# Power_Management.net
KiCad netlist of a schematic drawn in Altium Designer
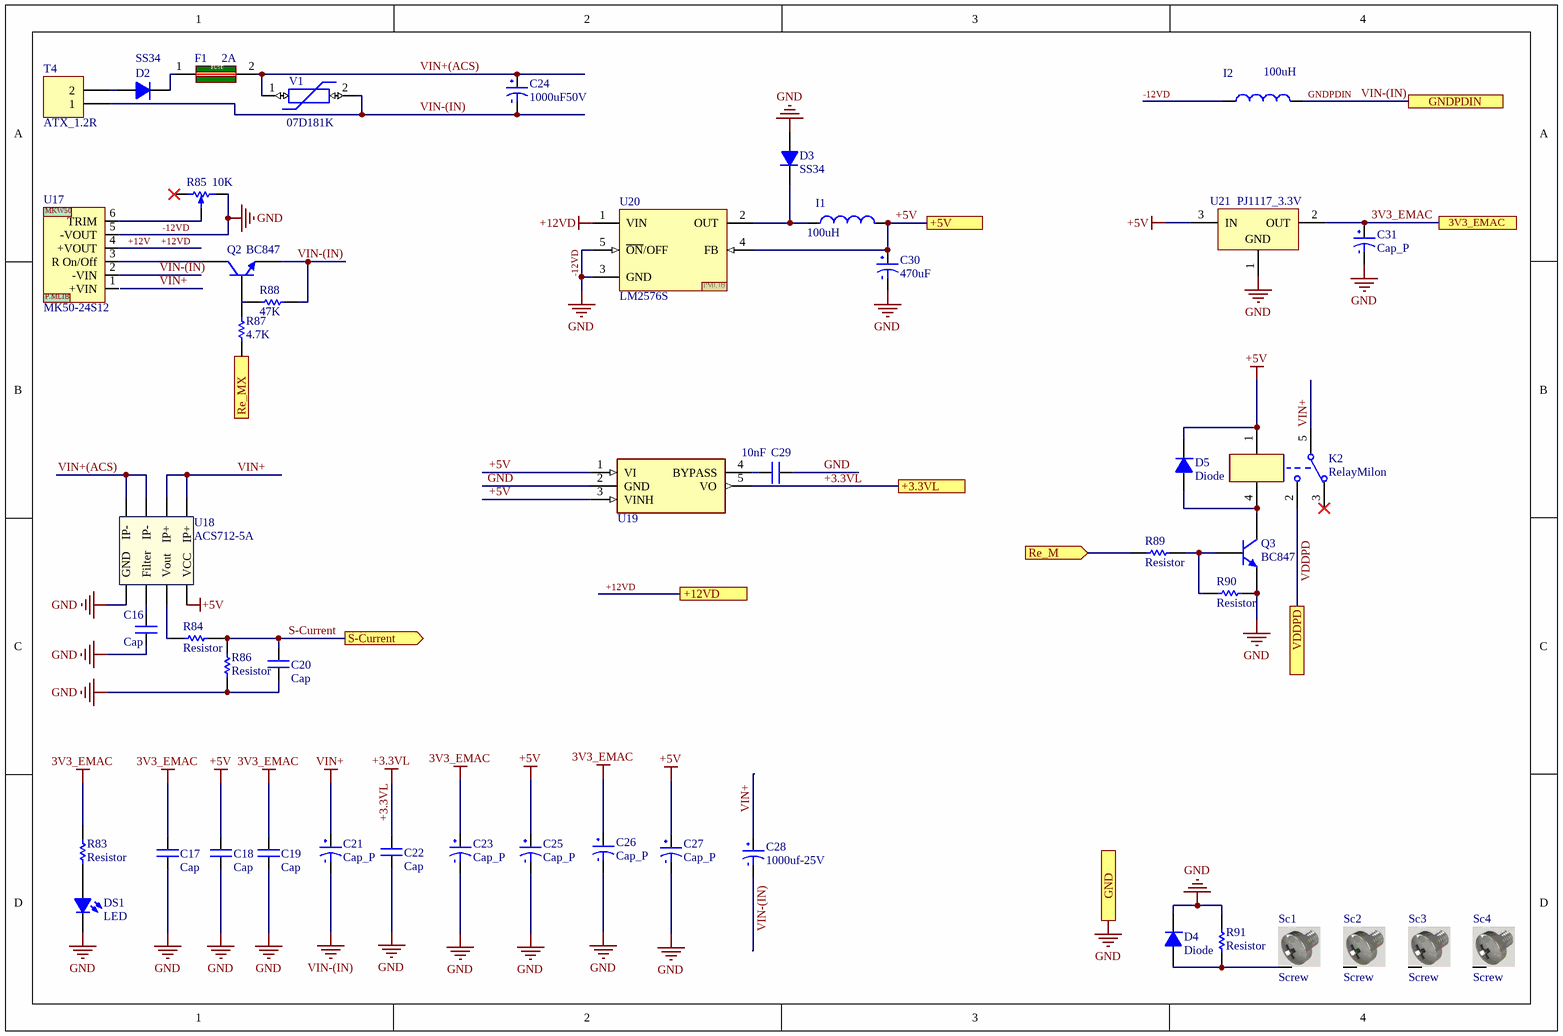
[diagram p0: Power Management.SchDoc]

(export (version "E")
  (design (tool "Eeschema 10.0.6"))
  (components
    (comp (ref "C16")
      (value "Cap")
      (footprint "Cap0805")
      (description "Surface mount Capacitor")
      (libsource (lib "PMLIB2020") (part "Cap"))
    )
    (comp (ref "C17")
      (value "Cap")
      (footprint "Cap0805")
      (description "Surface mount Capacitor")
      (libsource (lib "PMLIB2020") (part "Cap"))
    )
    (comp (ref "C18")
      (value "Cap")
      (footprint "Cap0805")
      (description "Surface mount Capacitor")
      (libsource (lib "PMLIB2020") (part "Cap"))
    )
    (comp (ref "C19")
      (value "Cap")
      (footprint "Cap0805")
      (description "Surface mount Capacitor")
      (libsource (lib "PMLIB2020") (part "Cap"))
    )
    (comp (ref "C20")
      (value "Cap")
      (footprint "Cap0805")
      (description "Surface mount Capacitor")
      (libsource (lib "PMLIB2020") (part "Cap"))
    )
    (comp (ref "C21")
      (value "Cap_P")
      (footprint "Cap_5mm")
      (description "Polarity")
      (libsource (lib "PMLIB2020") (part "Cap_P"))
    )
    (comp (ref "C22")
      (value "Cap")
      (footprint "Cap0805")
      (description "Surface mount Capacitor")
      (libsource (lib "PMLIB2020") (part "Cap"))
    )
    (comp (ref "C23")
      (value "Cap_P")
      (footprint "CAPMOL_C")
      (description "Polarity")
      (libsource (lib "PMLIB2020-V3") (part "Cap_P"))
    )
    (comp (ref "C24")
      (value "1000uF50V")
      (footprint "Cap_8mm")
      (description "Polarity")
      (libsource (lib "PMLIB2020-V3") (part "Cap_P"))
    )
    (comp (ref "C25")
      (value "Cap_P")
      (footprint "CAPMOL_C")
      (description "Polarity")
      (libsource (lib "PMLIB2020-V3") (part "Cap_P"))
    )
    (comp (ref "C26")
      (value "Cap_P")
      (footprint "CAPMOL_C")
      (description "Polarity")
      (libsource (lib "PMLIB2020-V3") (part "Cap_P"))
    )
    (comp (ref "C27")
      (value "Cap_P")
      (footprint "Cap_SMD")
      (description "Polarity")
      (libsource (lib "PMLIB2020-V3") (part "Cap_P"))
    )
    (comp (ref "C28")
      (value "1000uf-25V")
      (footprint "Cap_5mm")
      (description "Polarity")
      (libsource (lib "PMLIB2020") (part "Cap_P"))
    )
    (comp (ref "C29")
      (value "10nF")
      (footprint "Cap0805")
      (description "Surface mount Capacitor")
      (libsource (lib "PMLIB2020-V3") (part "Cap"))
    )
    (comp (ref "C30")
      (value "470uF")
      (footprint "Cap_4mm")
      (description "Polarity")
      (libsource (lib "PMLIB2020") (part "Cap_P"))
    )
    (comp (ref "C31")
      (value "Cap_P")
      (footprint "Cap_4mm")
      (description "Polarity")
      (libsource (lib "PMLIB2020") (part "Cap_P"))
    )
    (comp (ref "D2")
      (value "SS34")
      (footprint "Diod-1A-SMD")
      (description "Diode")
      (libsource (lib "PMLIB2020") (part "Diode"))
    )
    (comp (ref "D3")
      (value "SS34")
      (footprint "Diod-1A-SMD")
      (description "Diode")
      (libsource (lib "PMLIB2020") (part "Diode"))
    )
    (comp (ref "D4") (value "Diode") (footprint "Diod-1A-SMD") (libsource (lib "PMLIB2020") (part "Diode")))
    (comp (ref "D5")
      (value "Diode")
      (footprint "Diod-1A-SMD")
      (libsource (lib "PMLIB2020-V3") (part "Diode"))
    )
    (comp (ref "DS1") (value "LED") (footprint "Led0805") (libsource (lib "PMLIB2020") (part "LED")))
    (comp (ref "F1")
      (value "2A")
      (footprint "1206")
      (description "Fuse")
      (libsource (lib "PMLIB2020") (part "Fuse"))
    )
    (comp (ref "I1")
      (value "100uH")
      (footprint "Indicator_SMD")
      (description "Indicator")
      (libsource (lib "PMLIB2020") (part "Inductor"))
    )
    (comp (ref "I2")
      (value "100uH")
      (footprint "Indicator_10mH")
      (description "Indicator")
      (libsource (lib "PMLIB2020-V3") (part "Inductor"))
    )
    (comp (ref "K2")
      (value "RelayMilon")
      (footprint "RelayMinionSmall")
      (libsource (lib "PMLIB2020-V3") (part "RelayMilon"))
    )
    (comp (ref "Q2")
      (value "BC847")
      (footprint "SOT23_BEC_L")
      (description "NPN Bipolar Transistor")
      (fields (field (name "PUBLISHER") "Altium Limited"))
      (libsource (lib "PMLIB2020-V3") (part "NPN"))
    )
    (comp (ref "Q3")
      (value "BC847")
      (footprint "SOT23_BEC_L")
      (description "NPN Bipolar Transistor")
      (fields (field (name "PUBLISHER") "Altium Limited"))
      (libsource (lib "PMLIB2020-V3") (part "NPN"))
    )
    (comp (ref "R83") (value "Resistor") (footprint "R0805") (libsource (lib "PMLIB2020") (part "Resistor")))
    (comp (ref "R84") (value "Resistor") (footprint "R0805") (libsource (lib "PMLIB2020") (part "Resistor")))
    (comp (ref "R85")
      (value "10K")
      (footprint "POT4MM-Small Pot")
      (description "Square Trimming Potentiometer")
      (fields (field (name "Comment") "RPot SM") (field (name "PUBLISHER") "Altium Limited"))
      (libsource (lib "PMLIB2020-V3") (part "RPot SM"))
    )
    (comp (ref "R86") (value "Resistor") (footprint "R0805") (libsource (lib "PMLIB2020") (part "Resistor")))
    (comp (ref "R87")
      (value "4.7K")
      (footprint "R0805")
      (description "Resistor")
      (libsource (lib "PMLIB2020-V3") (part "Resistor"))
    )
    (comp (ref "R88")
      (value "47K")
      (footprint "R0805")
      (description "Resistor")
      (libsource (lib "PMLIB2020-V3") (part "Resistor"))
    )
    (comp (ref "R89")
      (value "Resistor")
      (footprint "R0805")
      (libsource (lib "PMLIB2020-V3") (part "Resistor"))
    )
    (comp (ref "R90")
      (value "Resistor")
      (footprint "R0805")
      (libsource (lib "PMLIB2020-V3") (part "Resistor"))
    )
    (comp (ref "R91") (value "Resistor") (footprint "0603") (libsource (lib "PMLIB2020") (part "Resistor")))
    (comp (ref "Sc1")
      (value "Screw")
      (footprint "Screw")
      (description "Screw 3mm")
      (libsource (lib "PMLIB2020") (part "Screw"))
    )
    (comp (ref "Sc2")
      (value "Screw")
      (footprint "Screw")
      (description "Screw 3mm")
      (libsource (lib "PMLIB2020") (part "Screw"))
    )
    (comp (ref "Sc3")
      (value "Screw")
      (footprint "Screw")
      (description "Screw 3mm")
      (libsource (lib "PMLIB2020") (part "Screw"))
    )
    (comp (ref "Sc4")
      (value "Screw")
      (footprint "Screw")
      (description "Screw 3mm")
      (libsource (lib "PMLIB2020") (part "Screw"))
    )
    (comp (ref "T4")
      (value "ATX_1.2R")
      (footprint "ATX_1.2S")
      (description "Connector")
      (libsource (lib "PMLIB2020-V3") (part "ATX_1.2R"))
    )
    (comp (ref "U17")
      (value "MK50-24S12")
      (footprint "MK50")
      (description "DCtoDC")
      (libsource (lib "PMLIB2020-V3") (part "MK50"))
    )
    (comp (ref "U18")
      (value "ACS712-5A")
      (footprint "SOP8")
      (description "Hall effect Current Sensor")
      (libsource (lib "PMLIB2020") (part "ACS712"))
    )
    (comp (ref "U19")
      (value "LD3985M33R")
      (footprint "SOT95P280X110-5N")
      (description "Linear Voltage Regulator IC 1 Output 150mA")
      (libsource (lib "PMLIB2020-V3") (part "LD3985M33R"))
    )
    (comp (ref "U20")
      (value "LM2576S")
      (footprint "LM2576S")
      (description "Regulator")
      (libsource (lib "PMLIB2020") (part "LM2576S"))
    )
    (comp (ref "U21")
      (value "PJ1117_3.3V")
      (footprint "PJ1117s")
      (description "Regulator")
      (libsource (lib "PMLIB2020-V3") (part "PJ1117_3.3V"))
    )
    (comp (ref "V1")
      (value "07D181K")
      (footprint "MOV-7D")
      (description "07D181K = 26V")
      (libsource (lib "PMLIB2020-V3") (part "MOV-07D"))
    )
  )
  (nets
    (net (code "1") (name "+3.3VL") (class "Default")
      (node (ref "C22") (pin "2") (pinfunction "2_2") (pintype "passive"))
      (node (ref "U19") (pin "5") (pinfunction "VO_5") (pintype "output"))
    )
    (net (code "2") (name "+5V") (class "Default")
      (node (ref "C18") (pin "2") (pinfunction "2_2") (pintype "passive"))
      (node (ref "C25") (pin "2") (pinfunction "2_2") (pintype "passive"))
      (node (ref "C27") (pin "2") (pinfunction "2_2") (pintype "passive"))
      (node (ref "C30") (pin "2") (pinfunction "2_2") (pintype "passive"))
      (node (ref "D5") (pin "K") (pinfunction "K_K") (pintype "passive"))
      (node (ref "I1") (pin "2") (pinfunction "2_2") (pintype "passive"))
      (node (ref "K2") (pin "1") (pinfunction "1_1") (pintype "passive"))
      (node (ref "U18") (pin "8") (pinfunction "VCC_8") (pintype "passive"))
      (node (ref "U19") (pin "1") (pinfunction "VI_1") (pintype "input"))
      (node (ref "U19") (pin "3") (pinfunction "VINH_3") (pintype "input"))
      (node (ref "U20") (pin "4") (pinfunction "FB_4") (pintype "input"))
      (node (ref "U21") (pin "3") (pinfunction "IN_3") (pintype "power_in"))
    )
    (net (code "3") (name "+12VD") (class "Default")
      (node (ref "U17") (pin "4") (pinfunction "+VOUT_4") (pintype "passive"))
      (node (ref "U20") (pin "1") (pinfunction "VIN_1") (pintype "power_in"))
    )
    (net (code "4") (name "/Re_M") (class "Default")
      (node (ref "R89") (pin "2") (pinfunction "2_2") (pintype "passive"))
    )
    (net (code "5") (name "/Re_MX") (class "Default")
      (node (ref "R87") (pin "2") (pinfunction "2_2") (pintype "passive"))
    )
    (net (code "6") (name "/S-Current") (class "Default")
      (node (ref "C20") (pin "2") (pinfunction "2_2") (pintype "passive"))
      (node (ref "R84") (pin "1") (pinfunction "1_1") (pintype "passive"))
      (node (ref "R86") (pin "1") (pinfunction "1_1") (pintype "passive"))
    )
    (net (code "7") (name "/VDDPD") (class "Default")
      (node (ref "K2") (pin "2") (pinfunction "2_2") (pintype "passive"))
    )
    (net (code "8") (name "/VIN+(ACS)") (class "Default")
      (node (ref "C24") (pin "2") (pinfunction "2_2") (pintype "passive"))
      (node (ref "F1") (pin "2") (pinfunction "OUT_2") (pintype "passive"))
      (node (ref "U18") (pin "3") (pinfunction "IP-_3") (pintype "passive"))
      (node (ref "U18") (pin "4") (pinfunction "IP-_4") (pintype "passive"))
      (node (ref "V1") (pin "1") (pinfunction "1_1") (pintype "bidirectional"))
    )
    (net (code "9") (name "3V3_EMAC") (class "Default")
      (node (ref "C17") (pin "2") (pinfunction "2_2") (pintype "passive"))
      (node (ref "C19") (pin "2") (pinfunction "2_2") (pintype "passive"))
      (node (ref "C23") (pin "2") (pinfunction "2_2") (pintype "passive"))
      (node (ref "C26") (pin "2") (pinfunction "2_2") (pintype "passive"))
      (node (ref "C31") (pin "2") (pinfunction "2_2") (pintype "passive"))
      (node (ref "R83") (pin "1") (pinfunction "1_1") (pintype "passive"))
      (node (ref "U21") (pin "2") (pinfunction "OUT_2") (pintype "power_in"))
    )
    (net (code "10") (name "GND") (class "Default")
      (node (ref "C16") (pin "1") (pinfunction "1_1") (pintype "passive"))
      (node (ref "C17") (pin "1") (pinfunction "1_1") (pintype "passive"))
      (node (ref "C18") (pin "1") (pinfunction "1_1") (pintype "passive"))
      (node (ref "C19") (pin "1") (pinfunction "1_1") (pintype "passive"))
      (node (ref "C20") (pin "1") (pinfunction "1_1") (pintype "passive"))
      (node (ref "C22") (pin "1") (pinfunction "1_1") (pintype "passive"))
      (node (ref "C23") (pin "1") (pinfunction "1_1") (pintype "passive"))
      (node (ref "C25") (pin "1") (pinfunction "1_1") (pintype "passive"))
      (node (ref "C26") (pin "1") (pinfunction "1_1") (pintype "passive"))
      (node (ref "C27") (pin "1") (pinfunction "1_1") (pintype "passive"))
      (node (ref "C29") (pin "2") (pinfunction "2_2") (pintype "passive"))
      (node (ref "C30") (pin "1") (pinfunction "1_1") (pintype "passive"))
      (node (ref "C31") (pin "1") (pinfunction "1_1") (pintype "passive"))
      (node (ref "D3") (pin "A") (pinfunction "A_A") (pintype "passive"))
      (node (ref "D4") (pin "K") (pinfunction "K_K") (pintype "passive"))
      (node (ref "DS1") (pin "K") (pinfunction "K_K") (pintype "passive"))
      (node (ref "I2") (pin "1") (pinfunction "1_1") (pintype "passive"))
      (node (ref "Q3") (pin "2") (pinfunction "E_2") (pintype "passive"))
      (node (ref "R85") (pin "CW") (pinfunction "+_CW") (pintype "passive"))
      (node (ref "R86") (pin "2") (pinfunction "2_2") (pintype "passive"))
      (node (ref "R90") (pin "1") (pinfunction "1_1") (pintype "passive"))
      (node (ref "R91") (pin "1") (pinfunction "1_1") (pintype "passive"))
      (node (ref "U17") (pin "5") (pinfunction "-VOUT_5") (pintype "passive"))
      (node (ref "U18") (pin "5") (pinfunction "GND_5") (pintype "passive"))
      (node (ref "U19") (pin "2") (pinfunction "GND_2") (pintype "power_in"))
      (node (ref "U20") (pin "3") (pinfunction "GND_3") (pintype "power_in"))
      (node (ref "U20") (pin "5") (pinfunction "~{ON}/OFF_5") (pintype "input"))
      (node (ref "U21") (pin "1") (pinfunction "GND_1") (pintype "power_in"))
    )
    (net (code "11") (name "Net-(D2-PadA)") (class "Default")
      (node (ref "D2") (pin "A") (pinfunction "A_A") (pintype "passive"))
      (node (ref "T4") (pin "2") (pinfunction "2_2") (pintype "passive"))
    )
    (net (code "12") (name "Net-(D4-PadA)") (class "Default")
      (node (ref "D4") (pin "A") (pinfunction "A_A") (pintype "passive"))
      (node (ref "R91") (pin "2") (pinfunction "2_2") (pintype "passive"))
      (node (ref "Sc1") (pin "S") (pinfunction "S_S") (pintype "passive"))
    )
    (net (code "13") (name "Net-(DS1-PadA)") (class "Default")
      (node (ref "DS1") (pin "A") (pinfunction "A_A") (pintype "passive"))
      (node (ref "R83") (pin "2") (pinfunction "2_2") (pintype "passive"))
    )
    (net (code "14") (name "Net-(F1-IN)") (class "Default")
      (node (ref "D2") (pin "K") (pinfunction "K_K") (pintype "passive"))
      (node (ref "F1") (pin "1") (pinfunction "IN_1") (pintype "passive"))
    )
    (net (code "15") (name "Net-(Q2-B)") (class "Default")
      (node (ref "Q2") (pin "1") (pinfunction "B_1") (pintype "passive"))
      (node (ref "R87") (pin "1") (pinfunction "1_1") (pintype "passive"))
      (node (ref "R88") (pin "2") (pinfunction "2_2") (pintype "passive"))
    )
    (net (code "16") (name "Net-(Q2-C)") (class "Default")
      (node (ref "Q2") (pin "3") (pinfunction "C_3") (pintype "passive"))
      (node (ref "U17") (pin "3") (pinfunction "R_On/Off_3") (pintype "passive"))
    )
    (net (code "17") (name "Net-(Q3-B)") (class "Default")
      (node (ref "Q3") (pin "1") (pinfunction "B_1") (pintype "passive"))
      (node (ref "R89") (pin "1") (pinfunction "1_1") (pintype "passive"))
      (node (ref "R90") (pin "2") (pinfunction "2_2") (pintype "passive"))
    )
    (net (code "18") (name "Net-(Q3-C)") (class "Default")
      (node (ref "D5") (pin "A") (pinfunction "A_A") (pintype "passive"))
      (node (ref "K2") (pin "4") (pinfunction "4_4") (pintype "passive"))
      (node (ref "Q3") (pin "3") (pinfunction "C_3") (pintype "passive"))
    )
    (net (code "19") (name "Net-(U17-TRIM)") (class "Default")
      (node (ref "R85") (pin "W") (pinfunction "W_W") (pintype "passive"))
      (node (ref "U17") (pin "6") (pinfunction "TRIM_6") (pintype "passive"))
    )
    (net (code "20") (name "Net-(U18-Filter)") (class "Default")
      (node (ref "C16") (pin "2") (pinfunction "2_2") (pintype "passive"))
      (node (ref "U18") (pin "6") (pinfunction "Filter_6") (pintype "passive"))
    )
    (net (code "21") (name "Net-(U18-Vout)") (class "Default")
      (node (ref "R84") (pin "2") (pinfunction "2_2") (pintype "passive"))
      (node (ref "U18") (pin "7") (pinfunction "Vout_7") (pintype "passive"))
    )
    (net (code "22") (name "Net-(U19-BYPASS)") (class "Default")
      (node (ref "C29") (pin "1") (pinfunction "1_1") (pintype "passive"))
      (node (ref "U19") (pin "4") (pinfunction "BYPASS_4") (pintype "passive"))
    )
    (net (code "23") (name "Net-(U20-OUT)") (class "Default")
      (node (ref "D3") (pin "K") (pinfunction "K_K") (pintype "passive"))
      (node (ref "I1") (pin "1") (pinfunction "1_1") (pintype "passive"))
      (node (ref "U20") (pin "2") (pinfunction "OUT_2") (pintype "power_in"))
    )
    (net (code "24") (name "VIN+") (class "Default")
      (node (ref "C21") (pin "2") (pinfunction "2_2") (pintype "passive"))
      (node (ref "C28") (pin "2") (pinfunction "2_2") (pintype "passive"))
      (node (ref "K2") (pin "5") (pinfunction "5_5") (pintype "passive"))
      (node (ref "U18") (pin "1") (pinfunction "IP+_1") (pintype "passive"))
      (node (ref "U18") (pin "2") (pinfunction "IP+_2") (pintype "passive"))
    )
    (net (code "25") (name "VIN-(IN)") (class "Default")
      (node (ref "C21") (pin "1") (pinfunction "1_1") (pintype "passive"))
      (node (ref "C24") (pin "1") (pinfunction "1_1") (pintype "passive"))
      (node (ref "C28") (pin "1") (pinfunction "1_1") (pintype "passive"))
      (node (ref "I2") (pin "2") (pinfunction "2_2") (pintype "passive"))
      (node (ref "Q2") (pin "2") (pinfunction "E_2") (pintype "passive"))
      (node (ref "R88") (pin "1") (pinfunction "1_1") (pintype "passive"))
      (node (ref "T4") (pin "1") (pinfunction "1_1") (pintype "passive"))
      (node (ref "U17") (pin "2") (pinfunction "-VIN_2") (pintype "passive"))
      (node (ref "V1") (pin "2") (pinfunction "2_2") (pintype "bidirectional"))
    )
    (net (code "26") (name "unconnected-(K2-Pad3)") (class "Default")
      (node (ref "K2") (pin "3") (pinfunction "3_3") (pintype "passive+no_connect"))
    )
    (net (code "27") (name "unconnected-(R85---PadCCW)") (class "Default")
      (node (ref "R85") (pin "CCW") (pinfunction "-_CCW") (pintype "passive+no_connect"))
    )
    (net (code "28") (name "unconnected-(Sc2-PadS)") (class "Default")
      (node (ref "Sc2") (pin "S") (pinfunction "S_S") (pintype "passive"))
    )
    (net (code "29") (name "unconnected-(Sc3-PadS)") (class "Default")
      (node (ref "Sc3") (pin "S") (pinfunction "S_S") (pintype "passive"))
    )
    (net (code "30") (name "unconnected-(Sc4-PadS)") (class "Default")
      (node (ref "Sc4") (pin "S") (pinfunction "S_S") (pintype "passive"))
    )
    (net (code "31") (name "unconnected-(U17-+VIN-Pad1)") (class "Default")
      (node (ref "U17") (pin "1") (pinfunction "+VIN_1") (pintype "passive"))
    )
  )
)
